# osi-blink_rev_0.net
KiCad netlist of a schematic drawn in EAGLE
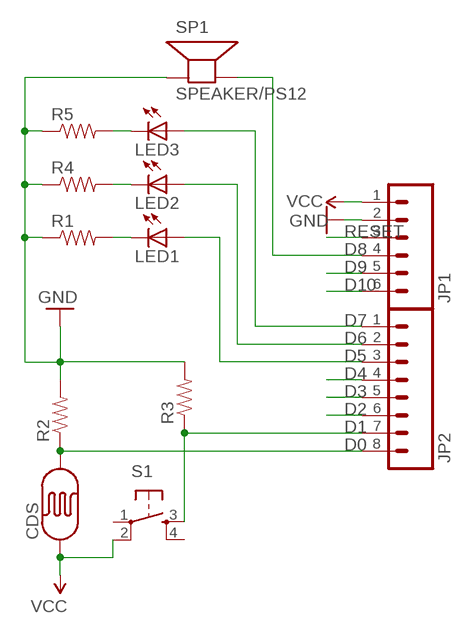
[diagram p0: schematic, sheet 1]

(export (version "E")
  (design (tool "Eeschema 10.0.6"))
  (components
    (comp (ref "CDS")
      (value "PHOTOCELLPTH-KIT")
      (footprint "eagle-import:PHOTOCELL-KIT")
      (libsource (lib "eagle-import") (part "PHOTOCELLPTH-KIT"))
    )
    (comp (ref "JP1")
      (value "M06SIP")
      (footprint "eagle-import:1X06")
      (libsource (lib "eagle-import") (part "M06SIP"))
    )
    (comp (ref "JP2")
      (value "M081X08")
      (footprint "eagle-import:1X08")
      (libsource (lib "eagle-import") (part "M081X08"))
    )
    (comp (ref "LED1")
      (value "LED3MM")
      (footprint "eagle-import:LED3MM")
      (libsource (lib "eagle-import") (part "LED3MM"))
    )
    (comp (ref "LED2")
      (value "LED3MM")
      (footprint "eagle-import:LED3MM")
      (libsource (lib "eagle-import") (part "LED3MM"))
    )
    (comp (ref "LED3")
      (value "LED3MM")
      (footprint "eagle-import:LED3MM")
      (libsource (lib "eagle-import") (part "LED3MM"))
    )
    (comp (ref "R1")
      (value "RESISTORKIT")
      (footprint "eagle-import:AXIAL-0.3-KIT")
      (libsource (lib "eagle-import") (part "RESISTORKIT"))
    )
    (comp (ref "R2")
      (value "RESISTORKIT")
      (footprint "eagle-import:AXIAL-0.3-KIT")
      (libsource (lib "eagle-import") (part "RESISTORKIT"))
    )
    (comp (ref "R3")
      (value "RESISTORKIT")
      (footprint "eagle-import:AXIAL-0.3-KIT")
      (libsource (lib "eagle-import") (part "RESISTORKIT"))
    )
    (comp (ref "R4")
      (value "RESISTORKIT")
      (footprint "eagle-import:AXIAL-0.3-KIT")
      (libsource (lib "eagle-import") (part "RESISTORKIT"))
    )
    (comp (ref "R5")
      (value "RESISTORKIT")
      (footprint "eagle-import:AXIAL-0.3-KIT")
      (libsource (lib "eagle-import") (part "RESISTORKIT"))
    )
    (comp (ref "S1")
      (value "TAC_SWITCHPTH")
      (footprint "eagle-import:TACTILE-PTH")
      (libsource (lib "eagle-import") (part "TAC_SWITCHPTH"))
    )
    (comp (ref "SP1")
      (value "SPEAKER/PS12")
      (footprint "eagle-import:PS12")
      (libsource (lib "eagle-import") (part "SPEAKER/PS12"))
    )
  )
  (nets
    (net (code "1") (name "/D0") (class "Default")
      (node (ref "CDS") (pin "2") (pinfunction "P$2_2") (pintype "bidirectional"))
      (node (ref "JP2") (pin "8") (pinfunction "8_8") (pintype "passive"))
      (node (ref "R2") (pin "P$1") (pinfunction "1_P$1") (pintype "passive"))
    )
    (net (code "2") (name "/D1") (class "Default")
      (node (ref "JP2") (pin "7") (pinfunction "7_7") (pintype "passive"))
      (node (ref "R3") (pin "P$1") (pinfunction "1_P$1") (pintype "passive"))
      (node (ref "S1") (pin "3") (pinfunction "3_3") (pintype "passive"))
    )
    (net (code "3") (name "/D2") (class "Default")
      (node (ref "JP2") (pin "6") (pinfunction "6_6") (pintype "passive"))
    )
    (net (code "4") (name "/D3") (class "Default")
      (node (ref "JP2") (pin "5") (pinfunction "5_5") (pintype "passive"))
    )
    (net (code "5") (name "/D4") (class "Default")
      (node (ref "JP2") (pin "4") (pinfunction "4_4") (pintype "passive"))
    )
    (net (code "6") (name "/D5") (class "Default")
      (node (ref "JP2") (pin "3") (pinfunction "3_3") (pintype "passive"))
      (node (ref "LED1") (pin "A") (pinfunction "A_A") (pintype "passive"))
    )
    (net (code "7") (name "/D6") (class "Default")
      (node (ref "JP2") (pin "2") (pinfunction "2_2") (pintype "passive"))
      (node (ref "LED2") (pin "A") (pinfunction "A_A") (pintype "passive"))
    )
    (net (code "8") (name "/D7") (class "Default")
      (node (ref "JP2") (pin "1") (pinfunction "1_1") (pintype "passive"))
      (node (ref "LED3") (pin "A") (pinfunction "A_A") (pintype "passive"))
    )
    (net (code "9") (name "/D8") (class "Default")
      (node (ref "JP1") (pin "4") (pinfunction "4_4") (pintype "passive"))
      (node (ref "SP1") (pin "P$2") (pinfunction "-_P$2") (pintype "passive"))
    )
    (net (code "10") (name "/D9") (class "Default")
      (node (ref "JP1") (pin "5") (pinfunction "5_5") (pintype "passive"))
    )
    (net (code "11") (name "/D10") (class "Default")
      (node (ref "JP1") (pin "6") (pinfunction "6_6") (pintype "passive"))
    )
    (net (code "12") (name "/RESET") (class "Default")
      (node (ref "JP1") (pin "3") (pinfunction "3_3") (pintype "passive"))
    )
    (net (code "13") (name "GND") (class "Default")
      (node (ref "JP1") (pin "2") (pinfunction "2_2") (pintype "passive"))
      (node (ref "R1") (pin "P$1") (pinfunction "1_P$1") (pintype "passive"))
      (node (ref "R2") (pin "P$2") (pinfunction "2_P$2") (pintype "passive"))
      (node (ref "R3") (pin "P$2") (pinfunction "2_P$2") (pintype "passive"))
      (node (ref "R4") (pin "P$1") (pinfunction "1_P$1") (pintype "passive"))
      (node (ref "R5") (pin "P$1") (pinfunction "1_P$1") (pintype "passive"))
      (node (ref "SP1") (pin "P$1") (pinfunction "+_P$1") (pintype "passive"))
    )
    (net (code "14") (name "Net-(LED1-C)") (class "Default")
      (node (ref "LED1") (pin "K") (pinfunction "C_K") (pintype "passive"))
      (node (ref "R1") (pin "P$2") (pinfunction "2_P$2") (pintype "passive"))
    )
    (net (code "15") (name "Net-(LED2-C)") (class "Default")
      (node (ref "LED2") (pin "K") (pinfunction "C_K") (pintype "passive"))
      (node (ref "R4") (pin "P$2") (pinfunction "2_P$2") (pintype "passive"))
    )
    (net (code "16") (name "Net-(LED3-C)") (class "Default")
      (node (ref "LED3") (pin "K") (pinfunction "C_K") (pintype "passive"))
      (node (ref "R5") (pin "P$2") (pinfunction "2_P$2") (pintype "passive"))
    )
    (net (code "17") (name "VCC") (class "Default")
      (node (ref "CDS") (pin "1") (pinfunction "P$1_1") (pintype "bidirectional"))
      (node (ref "JP1") (pin "1") (pinfunction "1_1") (pintype "passive"))
      (node (ref "S1") (pin "2") (pinfunction "2_2") (pintype "passive"))
    )
    (net (code "18") (name "unconnected-(S1-Pad1)") (class "Default")
      (node (ref "S1") (pin "1") (pinfunction "1_1") (pintype "passive"))
    )
    (net (code "19") (name "unconnected-(S1-Pad4)") (class "Default")
      (node (ref "S1") (pin "4") (pinfunction "4_4") (pintype "passive"))
    )
  )
)
